# PlantBuddy.net
KiCad netlist of a schematic drawn in EAGLE
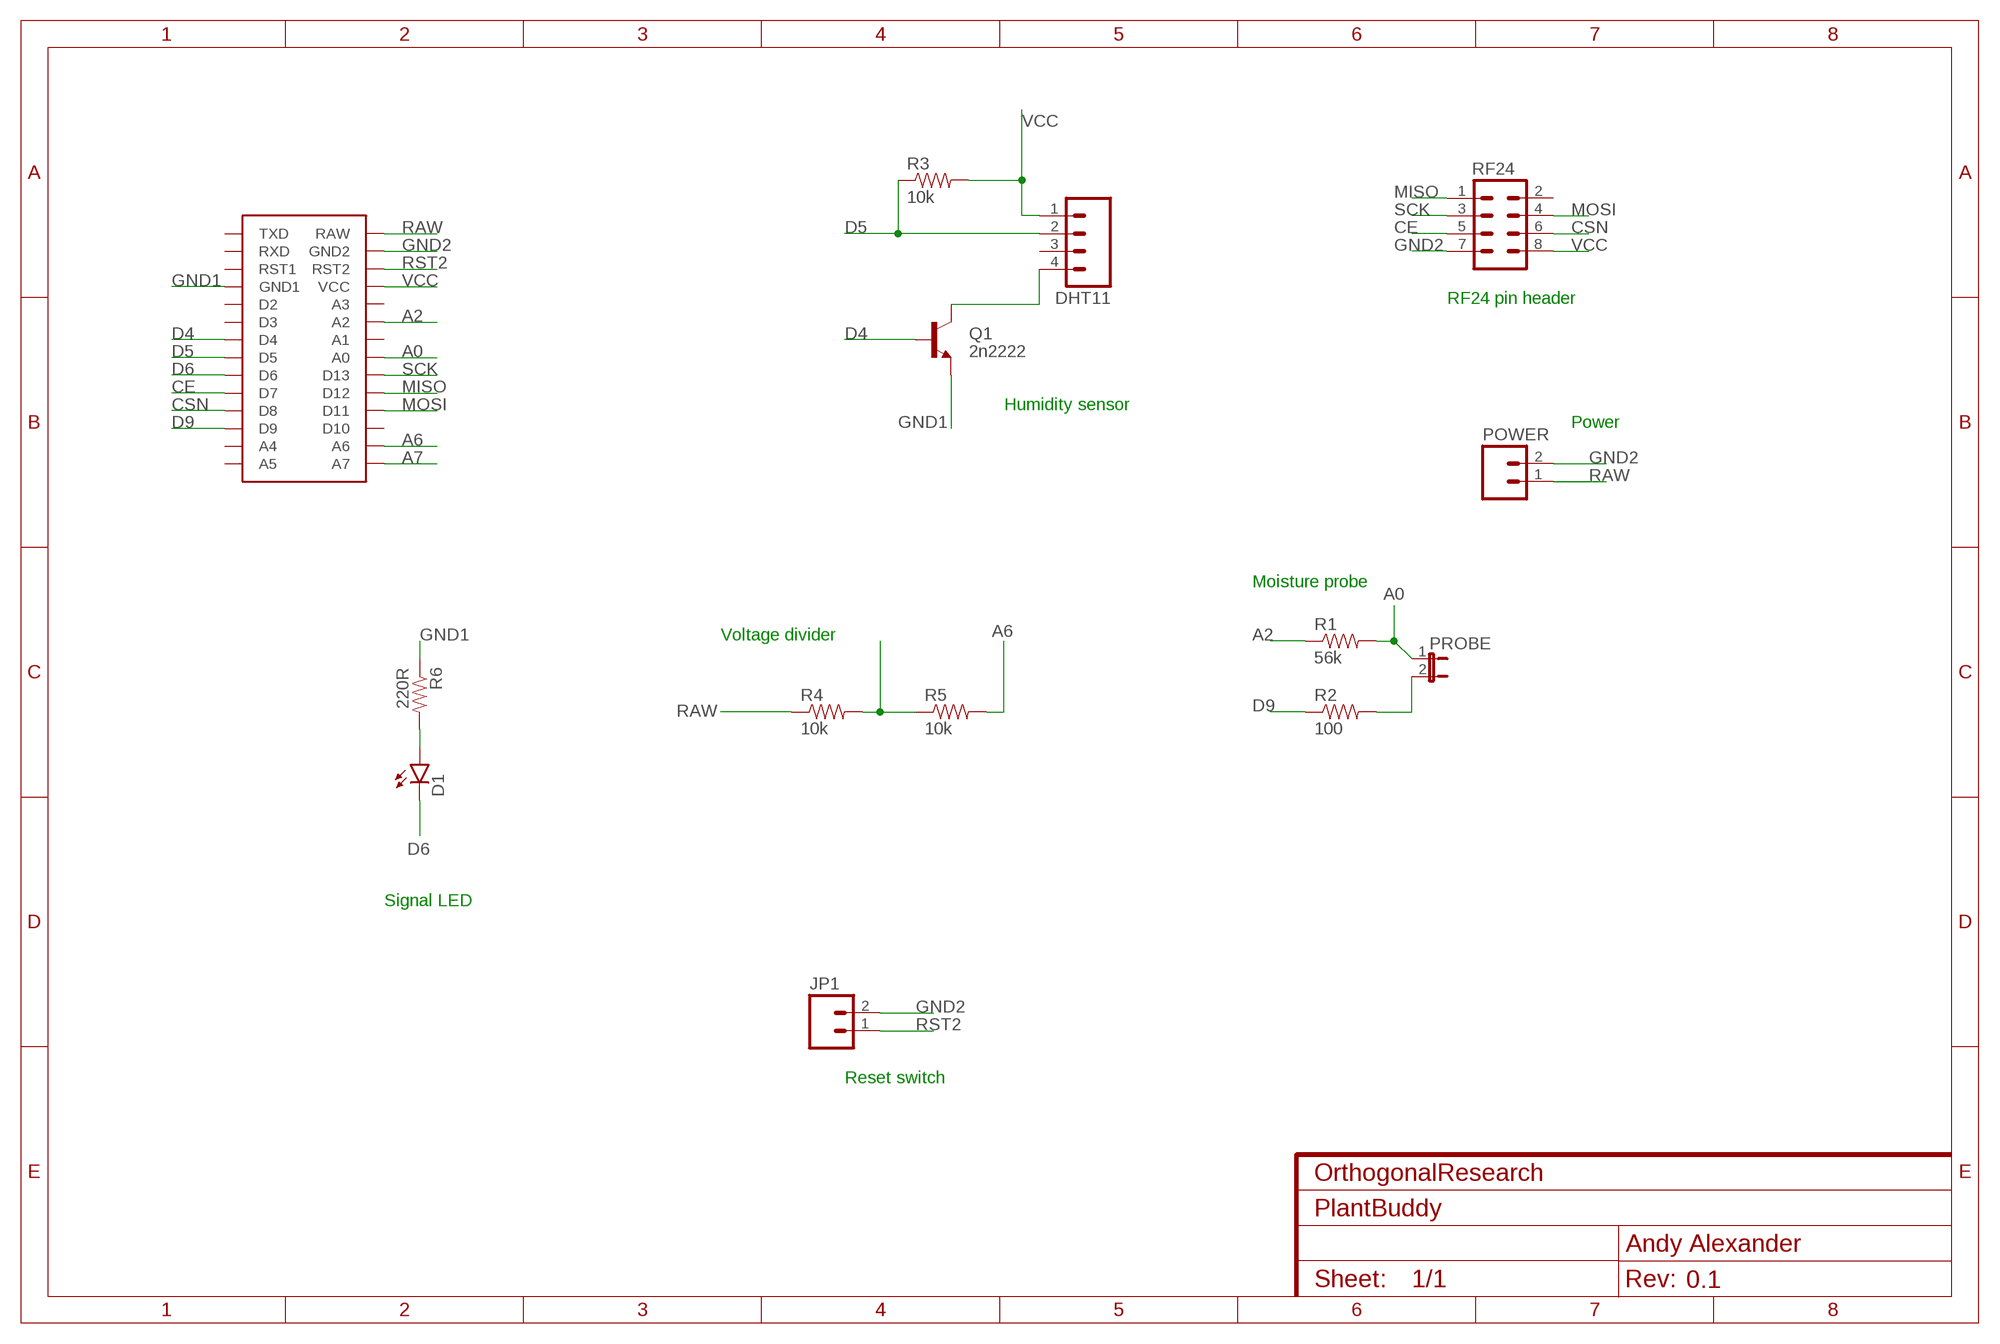
[diagram p0: schematic, sheet 1]

(export (version "E")
  (design (tool "Eeschema 10.0.6"))
  (components
    (comp (ref "D1")
      (value "LED5MM")
      (footprint "eagle-import:LED5MM")
      (libsource (lib "eagle-import") (part "LED5MM"))
    )
    (comp (ref "DHT11")
      (value "M04PTH")
      (footprint "eagle-import:1X04")
      (libsource (lib "eagle-import") (part "M04PTH"))
    )
    (comp (ref "JP1")
      (value "M021X02_NO_SILK")
      (footprint "eagle-import:1X02_NO_SILK")
      (libsource (lib "eagle-import") (part "M021X02_NO_SILK"))
    )
    (comp (ref "POWER")
      (value "M021X02_NO_SILK")
      (footprint "eagle-import:1X02_NO_SILK")
      (libsource (lib "eagle-import") (part "M021X02_NO_SILK"))
    )
    (comp (ref "PROBE")
      (value "JUMPER-2PTH")
      (footprint "eagle-import:1X02")
      (libsource (lib "eagle-import") (part "JUMPER-2PTH"))
    )
    (comp (ref "Q1")
      (value "2n2222")
      (footprint "eagle-import:TO-92-AMMO")
      (libsource (lib "eagle-import") (part "TRANSISTOR_NPNBC547"))
    )
    (comp (ref "R1")
      (value "56k")
      (footprint "eagle-import:AXIAL-0.3-KIT")
      (libsource (lib "eagle-import") (part "SparkFun-Resistors_RESISTORKIT"))
    )
    (comp (ref "R2")
      (value "100")
      (footprint "eagle-import:AXIAL-0.3-KIT")
      (libsource (lib "eagle-import") (part "SparkFun-Resistors_RESISTORKIT"))
    )
    (comp (ref "R3")
      (value "10k")
      (footprint "eagle-import:AXIAL-0.3-KIT")
      (libsource (lib "eagle-import") (part "SparkFun-Resistors_RESISTORKIT"))
    )
    (comp (ref "R4")
      (value "10k")
      (footprint "eagle-import:AXIAL-0.3-KIT")
      (libsource (lib "eagle-import") (part "SparkFun-Resistors_RESISTORKIT"))
    )
    (comp (ref "R5")
      (value "10k")
      (footprint "eagle-import:AXIAL-0.3-KIT")
      (libsource (lib "eagle-import") (part "SparkFun-Resistors_RESISTORKIT"))
    )
    (comp (ref "R6")
      (value "220R")
      (footprint "eagle-import:AXIAL-0.3-KIT")
      (libsource (lib "eagle-import") (part "RESISTORKIT"))
    )
    (comp (ref "RF24")
      (value "M04X2")
      (footprint "eagle-import:2X4")
      (libsource (lib "eagle-import") (part "M04X2"))
    )
    (comp (ref "U$1")
      (value "PRO-MINIPRO-MINI-328P_1")
      (footprint "eagle-import:PRO-MINI")
      (libsource (lib "eagle-import") (part "PRO-MINIPRO-MINI-328P_1"))
    )
  )
  (nets
    (net (code "1") (name "/A0") (class "Default")
      (node (ref "PROBE") (pin "1") (pinfunction "1_1") (pintype "passive"))
      (node (ref "R1") (pin "P$2") (pinfunction "2_P$2") (pintype "passive"))
      (node (ref "U$1") (pin "P$20") (pinfunction "A0_P$20") (pintype "bidirectional"))
    )
    (net (code "2") (name "/A2") (class "Default")
      (node (ref "R1") (pin "P$1") (pinfunction "1_P$1") (pintype "passive"))
      (node (ref "U$1") (pin "P$18") (pinfunction "A2_P$18") (pintype "bidirectional"))
    )
    (net (code "3") (name "/A6") (class "Default")
      (node (ref "R5") (pin "P$2") (pinfunction "2_P$2") (pintype "passive"))
      (node (ref "U$1") (pin "P$39") (pinfunction "A6_P$39") (pintype "bidirectional"))
    )
    (net (code "4") (name "/A7") (class "Default")
      (node (ref "R4") (pin "P$2") (pinfunction "2_P$2") (pintype "passive"))
      (node (ref "R5") (pin "P$1") (pinfunction "1_P$1") (pintype "passive"))
      (node (ref "U$1") (pin "P$40") (pinfunction "A7_P$40") (pintype "bidirectional"))
    )
    (net (code "5") (name "/CE") (class "Default")
      (node (ref "RF24") (pin "5") (pinfunction "5_5") (pintype "passive"))
      (node (ref "U$1") (pin "P$10") (pinfunction "D7_P$10") (pintype "bidirectional"))
    )
    (net (code "6") (name "/CSN") (class "Default")
      (node (ref "RF24") (pin "6") (pinfunction "6_6") (pintype "passive"))
      (node (ref "U$1") (pin "P$11") (pinfunction "D8_P$11") (pintype "bidirectional"))
    )
    (net (code "7") (name "/D4") (class "Default")
      (node (ref "Q1") (pin "2") (pinfunction "B_2") (pintype "passive"))
      (node (ref "U$1") (pin "P$7") (pinfunction "D4_P$7") (pintype "bidirectional"))
    )
    (net (code "8") (name "/D5") (class "Default")
      (node (ref "DHT11") (pin "2") (pinfunction "2_2") (pintype "passive"))
      (node (ref "R3") (pin "P$1") (pinfunction "1_P$1") (pintype "passive"))
      (node (ref "U$1") (pin "P$8") (pinfunction "D5_P$8") (pintype "bidirectional"))
    )
    (net (code "9") (name "/D6") (class "Default")
      (node (ref "D1") (pin "K") (pinfunction "C_K") (pintype "passive"))
      (node (ref "U$1") (pin "P$9") (pinfunction "D6_P$9") (pintype "bidirectional"))
    )
    (net (code "10") (name "/D9") (class "Default")
      (node (ref "R2") (pin "P$1") (pinfunction "1_P$1") (pintype "passive"))
      (node (ref "U$1") (pin "P$12") (pinfunction "D9_P$12") (pintype "bidirectional"))
    )
    (net (code "11") (name "/GND1") (class "Default")
      (node (ref "Q1") (pin "3") (pinfunction "E_3") (pintype "passive"))
      (node (ref "R6") (pin "P$1") (pinfunction "1_P$1") (pintype "passive"))
      (node (ref "U$1") (pin "P$4") (pinfunction "GND1_P$4") (pintype "power_in"))
    )
    (net (code "12") (name "/GND2") (class "Default")
      (node (ref "JP1") (pin "2") (pinfunction "2_2") (pintype "passive"))
      (node (ref "POWER") (pin "2") (pinfunction "2_2") (pintype "passive"))
      (node (ref "RF24") (pin "7") (pinfunction "7_7") (pintype "passive"))
      (node (ref "U$1") (pin "P$14") (pinfunction "GND2_P$14") (pintype "power_in"))
    )
    (net (code "13") (name "/MISO") (class "Default")
      (node (ref "RF24") (pin "1") (pinfunction "1_1") (pintype "passive"))
      (node (ref "U$1") (pin "P$22") (pinfunction "D12_P$22") (pintype "bidirectional"))
    )
    (net (code "14") (name "/MOSI") (class "Default")
      (node (ref "RF24") (pin "4") (pinfunction "4_4") (pintype "passive"))
      (node (ref "U$1") (pin "P$23") (pinfunction "D11_P$23") (pintype "bidirectional"))
    )
    (net (code "15") (name "/RAW") (class "Default")
      (node (ref "POWER") (pin "1") (pinfunction "1_1") (pintype "passive"))
      (node (ref "R4") (pin "P$1") (pinfunction "1_P$1") (pintype "passive"))
      (node (ref "U$1") (pin "P$13") (pinfunction "RAW_P$13") (pintype "power_in"))
    )
    (net (code "16") (name "/RST2") (class "Default")
      (node (ref "JP1") (pin "1") (pinfunction "1_1") (pintype "passive"))
      (node (ref "U$1") (pin "P$15") (pinfunction "RST2_P$15") (pintype "input"))
    )
    (net (code "17") (name "/SCK") (class "Default")
      (node (ref "RF24") (pin "3") (pinfunction "3_3") (pintype "passive"))
      (node (ref "U$1") (pin "P$21") (pinfunction "D13_P$21") (pintype "bidirectional"))
    )
    (net (code "18") (name "/VCC") (class "Default")
      (node (ref "DHT11") (pin "1") (pinfunction "1_1") (pintype "passive"))
      (node (ref "R3") (pin "P$2") (pinfunction "2_P$2") (pintype "passive"))
      (node (ref "RF24") (pin "8") (pinfunction "8_8") (pintype "passive"))
      (node (ref "U$1") (pin "P$16") (pinfunction "VCC_P$16") (pintype "power_in"))
    )
    (net (code "19") (name "Net-(Q1-C)") (class "Default")
      (node (ref "DHT11") (pin "4") (pinfunction "4_4") (pintype "passive"))
      (node (ref "Q1") (pin "1") (pinfunction "C_1") (pintype "passive"))
    )
    (net (code "20") (name "Net-(R2-2)") (class "Default")
      (node (ref "PROBE") (pin "2") (pinfunction "2_2") (pintype "passive"))
      (node (ref "R2") (pin "P$2") (pinfunction "2_P$2") (pintype "passive"))
    )
    (net (code "21") (name "Net-(R6-2)") (class "Default")
      (node (ref "D1") (pin "A") (pinfunction "A_A") (pintype "passive"))
      (node (ref "R6") (pin "P$2") (pinfunction "2_P$2") (pintype "passive"))
    )
    (net (code "22") (name "unconnected-(DHT11-Pad3)") (class "Default")
      (node (ref "DHT11") (pin "3") (pinfunction "3_3") (pintype "passive"))
    )
    (net (code "23") (name "unconnected-(RF24-Pad2)") (class "Default")
      (node (ref "RF24") (pin "2") (pinfunction "2_2") (pintype "passive"))
    )
    (net (code "24") (name "unconnected-(U$1-A1-PadP$19)") (class "Default")
      (node (ref "U$1") (pin "P$19") (pinfunction "A1_P$19") (pintype "bidirectional"))
    )
    (net (code "25") (name "unconnected-(U$1-A3-PadP$17)") (class "Default")
      (node (ref "U$1") (pin "P$17") (pinfunction "A3_P$17") (pintype "bidirectional"))
    )
    (net (code "26") (name "unconnected-(U$1-A4-PadP$34)") (class "Default")
      (node (ref "U$1") (pin "P$34") (pinfunction "A4_P$34") (pintype "bidirectional"))
    )
    (net (code "27") (name "unconnected-(U$1-A5-PadP$35)") (class "Default")
      (node (ref "U$1") (pin "P$35") (pinfunction "A5_P$35") (pintype "bidirectional"))
    )
    (net (code "28") (name "unconnected-(U$1-D2-PadP$5)") (class "Default")
      (node (ref "U$1") (pin "P$5") (pinfunction "D2_P$5") (pintype "bidirectional"))
    )
    (net (code "29") (name "unconnected-(U$1-D3-PadP$6)") (class "Default")
      (node (ref "U$1") (pin "P$6") (pinfunction "D3_P$6") (pintype "bidirectional"))
    )
    (net (code "30") (name "unconnected-(U$1-D10-PadP$24)") (class "Default")
      (node (ref "U$1") (pin "P$24") (pinfunction "D10_P$24") (pintype "bidirectional"))
    )
    (net (code "31") (name "unconnected-(U$1-RST1-PadP$3)") (class "Default")
      (node (ref "U$1") (pin "P$3") (pinfunction "RST1_P$3") (pintype "input"))
    )
    (net (code "32") (name "unconnected-(U$1-RXD-PadP$2)") (class "Default")
      (node (ref "U$1") (pin "P$2") (pinfunction "RXD_P$2") (pintype "bidirectional"))
    )
    (net (code "33") (name "unconnected-(U$1-TXD-PadTDX)") (class "Default")
      (node (ref "U$1") (pin "TDX") (pinfunction "TXD_TDX") (pintype "bidirectional"))
    )
  )
)
